# NiHAAx1to6.net
KiCad netlist of a schematic drawn in Altium Designer
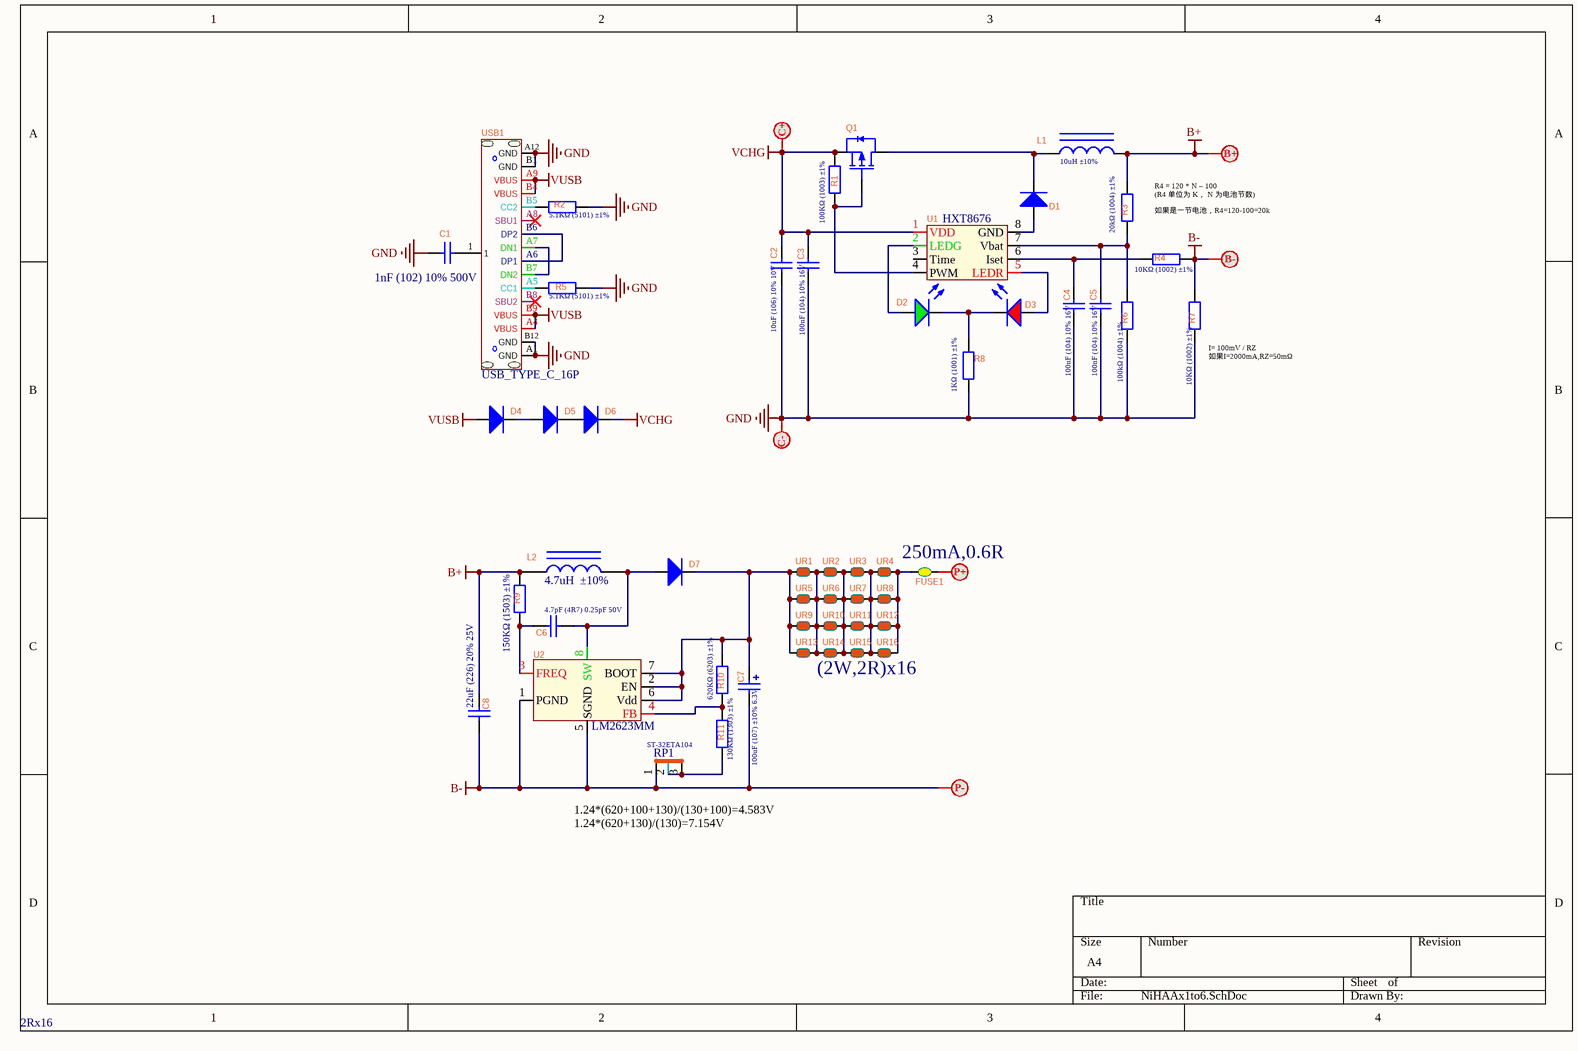
[diagram p0: NiHAAx1to6.SchDoc]

(export (version "E")
  (design (tool "Eeschema 10.0.6"))
  (components
    (comp (ref "B+1") (value "B+") (footprint "TAP") (libsource (lib "NiHAAx1to6") (part "B+")))
    (comp (ref "B-1") (value "B-") (footprint "TAP") (libsource (lib "NiHAAx1to6") (part "B-")))
    (comp (ref "C+1") (value "C+") (footprint "TAP") (libsource (lib "NiHAAx1to6") (part "C+")))
    (comp (ref "C-1") (value "C-") (footprint "TAP") (libsource (lib "NiHAAx1to6") (part "C-")))
    (comp (ref "C1")
      (value "1nF (102) 10% 500V")
      (footprint "1206_C")
      (description "贴片电容")
      (libsource (lib "Miscellaneous Devices LC") (part "1206 1nF (102) 10% 500V"))
    )
    (comp (ref "C2")
      (value "10uF (106) 10% 10V")
      (footprint "0603_C")
      (description "贴片电容")
      (libsource (lib "Miscellaneous Devices LC") (part "0603 10uF (106) 10% 10V"))
    )
    (comp (ref "C3")
      (value "100nF (104) 10% 16V")
      (footprint "0402_C")
      (description "贴片电容")
      (libsource (lib "Miscellaneous Devices LC") (part "0402 100nF (104) 10% 16V"))
    )
    (comp (ref "C4")
      (value "100nF (104) 10% 16V")
      (footprint "0402_C")
      (description "贴片电容")
      (libsource (lib "Miscellaneous Devices LC") (part "0402 100nF (104) 10% 16V"))
    )
    (comp (ref "C5")
      (value "100nF (104) 10% 16V")
      (footprint "0402_C")
      (description "贴片电容")
      (libsource (lib "Miscellaneous Devices LC") (part "0402 100nF (104) 10% 16V"))
    )
    (comp (ref "C6")
      (value "4.7pF (4R7) 0.25pF 50V")
      (footprint "0402_C")
      (description "贴片电容")
      (libsource (lib "Miscellaneous Devices LC") (part "0402 4.7pF (4R7) 0.25pF 50V"))
    )
    (comp (ref "C7")
      (value "100uF (107) ±10% 6.3V")
      (footprint "CASE-B_3528")
      (description "钽电容")
      (libsource (lib "Miscellaneous Devices LC") (part "3528 100uF (107) 10% 6.3V"))
    )
    (comp (ref "C8")
      (value "22uF (226) 20% 25V")
      (footprint "0805_C")
      (description "贴片电容")
      (libsource (lib "Miscellaneous Devices LC") (part "0805 22uF (226) 20% 25V"))
    )
    (comp (ref "D1")
      (value "M7")
      (footprint "CMS01")
      (description "二极管")
      (libsource (lib "Miscellaneous Devices LC") (part "SMA(DO-214AC) M7"))
    )
    (comp (ref "D2")
      (value "绿灯 0603")
      (footprint "0603_LED_S1")
      (description "发光二极管")
      (libsource (lib "Miscellaneous Devices LC") (part "0603 绿灯"))
    )
    (comp (ref "D3")
      (value "红灯 0603")
      (footprint "0603_LED_S1")
      (description "发光二极管")
      (libsource (lib "Miscellaneous Devices LC") (part "0603 红灯"))
    )
    (comp (ref "D4")
      (value "M7")
      (footprint "CMS01")
      (description "二极管")
      (libsource (lib "Miscellaneous Devices LC") (part "SMA(DO-214AC) M7"))
    )
    (comp (ref "D5")
      (value "M7")
      (footprint "CMS01")
      (description "二极管")
      (libsource (lib "Miscellaneous Devices LC") (part "SMA(DO-214AC) M7"))
    )
    (comp (ref "D6")
      (value "M7")
      (footprint "CMS01")
      (description "二极管")
      (libsource (lib "Miscellaneous Devices LC") (part "SMA(DO-214AC) M7"))
    )
    (comp (ref "D7")
      (value "M7")
      (footprint "CMS01")
      (description "二极管")
      (libsource (lib "Miscellaneous Devices LC") (part "SMA(DO-214AC) M7"))
    )
    (comp (ref "FUSE1")
      (value "OMF125")
      (footprint "2512")
      (description "3404.0006.22 OMF125 250mA OMF125 SCHURTER 贴装快速熔断保险丝")
      (libsource (lib "NiHAAx1to6") (part "FUSE"))
    )
    (comp (ref "L1")
      (value "10uH ±10%")
      (footprint "1206_L")
      (description "贴片电感")
      (libsource (lib "Miscellaneous Devices LC") (part "1206 10uH 10%"))
    )
    (comp (ref "L2")
      (value "4.7uH  ±10%")
      (footprint "1206_L")
      (description "贴片电感")
      (libsource (lib "Miscellaneous Devices LC") (part "1206 4.7uH  10%"))
    )
    (comp (ref "P+1") (value "P+") (footprint "TAP") (libsource (lib "NiHAAx1to6") (part "P+")))
    (comp (ref "P-1") (value "P-") (footprint "TAP") (libsource (lib "NiHAAx1to6") (part "P-")))
    (comp (ref "Q1")
      (value "AO3401A P道沟 X13A15 SOT-23")
      (footprint "SOT-23-3L")
      (description "MOS(场效应管)")
      (libsource (lib "Miscellaneous Devices LC") (part "AO3401A P道沟 X13A15 SOT-23"))
    )
    (comp (ref "R1")
      (value "100KΩ (1003) ±1%")
      (footprint "0402_R")
      (description "贴片电阻")
      (libsource (lib "Miscellaneous Devices LC") (part "0402 100KΩ (1003) 1%"))
    )
    (comp (ref "R2")
      (value "5.1KΩ (5101) ±1%")
      (footprint "0402_R")
      (description "贴片电阻")
      (libsource (lib "Miscellaneous Devices LC") (part "0402 5.1KΩ (5101) 1%"))
    )
    (comp (ref "R3")
      (value "20kΩ (1004) ±1%")
      (footprint "0402_R")
      (description "贴片电阻")
      (libsource (lib "Miscellaneous Devices LC") (part "0402 1MΩ (1004) 1%"))
    )
    (comp (ref "R4")
      (value "10KΩ (1002) ±1%")
      (footprint "0402_R")
      (description "贴片电阻")
      (libsource (lib "") (part "0402 10KΩ (1002) 1%_1"))
    )
    (comp (ref "R5")
      (value "5.1KΩ (5101) ±1%")
      (footprint "0402_R")
      (description "贴片电阻")
      (libsource (lib "Miscellaneous Devices LC") (part "0402 5.1KΩ (5101) 1%"))
    )
    (comp (ref "R6")
      (value "100kΩ (1004) ±1%")
      (footprint "0402_R")
      (description "贴片电阻")
      (libsource (lib "") (part "0402 1MΩ (1004) 1%_1"))
    )
    (comp (ref "R7")
      (value "10KΩ (1002) ±1%")
      (footprint "0805_R")
      (description "贴片电阻")
      (libsource (lib "Miscellaneous Devices LC") (part "0402 10KΩ (1002) 1%"))
    )
    (comp (ref "R8")
      (value "1KΩ (1001) ±1%")
      (footprint "0402_R")
      (description "贴片电阻")
      (libsource (lib "Miscellaneous Devices LC") (part "0402 1KΩ (1001) 1%"))
    )
    (comp (ref "R9")
      (value "150KΩ (1503) ±1%")
      (footprint "0402_R")
      (description "贴片电阻")
      (libsource (lib "Miscellaneous Devices LC") (part "0402 150KΩ (1503) 1%"))
    )
    (comp (ref "R10")
      (value "620KΩ (6203) ±1%")
      (footprint "0603_R")
      (description "贴片电阻")
      (libsource (lib "Miscellaneous Devices LC") (part "0603 620KΩ (6203) 1%"))
    )
    (comp (ref "R11")
      (value "130KΩ (1303) ±1%")
      (footprint "0603_R")
      (description "贴片电阻")
      (libsource (lib "Miscellaneous Devices LC") (part "0603 130KΩ (1303) 1%"))
    )
    (comp (ref "RP1")
      (value "ST-32ETA104")
      (footprint "ST-32ETA104")
      (description "3X3 SMD可调电阻 贴片电位器")
      (libsource (lib "NiHAAx1to6") (part "RP"))
    )
    (comp (ref "U1")
      (value "HXT8676")
      (footprint "SOP-8_150mil")
      (description "镍氢电池充电 IC")
      (libsource (lib "NiHAAx1to6") (part "HXT8676"))
    )
    (comp (ref "U2")
      (value "LM2623MM")
      (footprint "VSSOP8_3×3mm")
      (description "3 General-Purpose, Gated-Oscillator-Based DC-DC Boost Converter")
      (libsource (lib "NiHAAx1to6") (part "LM2623"))
    )
    (comp (ref "UR1") (value "R") (footprint "2512") (libsource (lib "NiHAAx1to6") (part "R")))
    (comp (ref "UR2") (value "R") (footprint "2512") (libsource (lib "NiHAAx1to6") (part "R")))
    (comp (ref "UR3") (value "R") (footprint "2512") (libsource (lib "NiHAAx1to6") (part "R")))
    (comp (ref "UR4") (value "R") (footprint "2512") (libsource (lib "NiHAAx1to6") (part "R")))
    (comp (ref "UR5") (value "R") (footprint "2512") (libsource (lib "NiHAAx1to6") (part "R")))
    (comp (ref "UR6") (value "R") (footprint "2512") (libsource (lib "NiHAAx1to6") (part "R")))
    (comp (ref "UR7") (value "R") (footprint "2512") (libsource (lib "NiHAAx1to6") (part "R")))
    (comp (ref "UR8") (value "R") (footprint "2512") (libsource (lib "NiHAAx1to6") (part "R")))
    (comp (ref "UR9") (value "R") (footprint "2512") (libsource (lib "NiHAAx1to6") (part "R")))
    (comp (ref "UR10") (value "R") (footprint "2512") (libsource (lib "NiHAAx1to6") (part "R")))
    (comp (ref "UR11") (value "R") (footprint "2512") (libsource (lib "NiHAAx1to6") (part "R")))
    (comp (ref "UR12") (value "R") (footprint "2512") (libsource (lib "NiHAAx1to6") (part "R")))
    (comp (ref "UR13") (value "R") (footprint "2512") (libsource (lib "NiHAAx1to6") (part "R")))
    (comp (ref "UR14") (value "R") (footprint "2512") (libsource (lib "NiHAAx1to6") (part "R")))
    (comp (ref "UR15") (value "R") (footprint "2512") (libsource (lib "NiHAAx1to6") (part "R")))
    (comp (ref "UR16") (value "R") (footprint "2512") (libsource (lib "NiHAAx1to6") (part "R")))
    (comp (ref "USB1")
      (value "USB_TYPE_C_16P")
      (footprint "USB Type-C-16Pin_A")
      (libsource (lib "OET") (part "USB_TYPE_C_16P"))
    )
  )
  (nets
    (net (code "1") (name "B+") (class "Default")
      (node (ref "B+1") (pin "1") (pinfunction "B+_1") (pintype "passive"))
      (node (ref "C8") (pin "2") (pinfunction "2_2") (pintype "passive"))
      (node (ref "L1") (pin "2") (pinfunction "2_2") (pintype "passive"))
      (node (ref "L2") (pin "1") (pinfunction "1_1") (pintype "passive"))
      (node (ref "R3") (pin "2") (pinfunction "2_2") (pintype "passive"))
      (node (ref "R9") (pin "2") (pinfunction "2_2") (pintype "passive"))
    )
    (net (code "2") (name "B-") (class "Default")
      (node (ref "B-1") (pin "1") (pinfunction "B-_1") (pintype "passive"))
      (node (ref "C7") (pin "2") (pinfunction "2_2") (pintype "passive"))
      (node (ref "C8") (pin "1") (pinfunction "1_1") (pintype "passive"))
      (node (ref "P-1") (pin "1") (pinfunction "P-_1") (pintype "passive"))
      (node (ref "R4") (pin "2") (pinfunction "2_2") (pintype "passive"))
      (node (ref "R7") (pin "2") (pinfunction "2_2") (pintype "passive"))
      (node (ref "RP1") (pin "1") (pintype "passive"))
      (node (ref "U2") (pin "1") (pinfunction "PGND_1") (pintype "passive"))
      (node (ref "U2") (pin "5") (pinfunction "SGND_5") (pintype "passive"))
    )
    (net (code "3") (name "GND") (class "Default")
      (node (ref "C-1") (pin "1") (pinfunction "C-_1") (pintype "passive"))
      (node (ref "C1") (pin "2") (pinfunction "2_2") (pintype "passive"))
      (node (ref "C2") (pin "1") (pinfunction "1_1") (pintype "passive"))
      (node (ref "C3") (pin "1") (pinfunction "1_1") (pintype "passive"))
      (node (ref "C4") (pin "1") (pinfunction "1_1") (pintype "passive"))
      (node (ref "C5") (pin "1") (pinfunction "1_1") (pintype "passive"))
      (node (ref "R2") (pin "1") (pinfunction "1_1") (pintype "passive"))
      (node (ref "R5") (pin "1") (pinfunction "1_1") (pintype "passive"))
      (node (ref "R6") (pin "2") (pinfunction "2_2") (pintype "passive"))
      (node (ref "R7") (pin "1") (pinfunction "1_1") (pintype "passive"))
      (node (ref "R8") (pin "1") (pinfunction "1_1") (pintype "passive"))
      (node (ref "USB1") (pin "A1") (pinfunction "GND_A1") (pintype "passive"))
      (node (ref "USB1") (pin "A12") (pinfunction "GND_A12") (pintype "passive"))
      (node (ref "USB1") (pin "B1") (pinfunction "GND_B1") (pintype "passive"))
      (node (ref "USB1") (pin "B12") (pinfunction "GND_B12") (pintype "passive"))
    )
    (net (code "4") (name "Net-(C1-Pad1)") (class "Default")
      (node (ref "C1") (pin "1") (pinfunction "1_1") (pintype "passive"))
      (node (ref "USB1") (pin "1") (pinfunction "1_1") (pintype "passive"))
    )
    (net (code "5") (name "Net-(D1-A)") (class "Default")
      (node (ref "D1") (pin "1") (pinfunction "A_1") (pintype "passive"))
      (node (ref "U1") (pin "8") (pinfunction "GND_8") (pintype "passive"))
    )
    (net (code "6") (name "Net-(D1-K)") (class "Default")
      (node (ref "D1") (pin "2") (pinfunction "K_2") (pintype "passive"))
      (node (ref "L1") (pin "1") (pinfunction "1_1") (pintype "passive"))
      (node (ref "Q1") (pin "3") (pinfunction "D_3") (pintype "passive"))
    )
    (net (code "7") (name "Net-(D2-PadK)") (class "Default")
      (node (ref "D2") (pin "K") (pinfunction "K_K") (pintype "passive"))
      (node (ref "D3") (pin "K") (pinfunction "K_K") (pintype "passive"))
      (node (ref "R8") (pin "2") (pinfunction "2_2") (pintype "passive"))
    )
    (net (code "8") (name "Net-(D4-K)") (class "Default")
      (node (ref "D4") (pin "2") (pinfunction "K_2") (pintype "passive"))
      (node (ref "D5") (pin "1") (pinfunction "A_1") (pintype "passive"))
    )
    (net (code "9") (name "Net-(D5-K)") (class "Default")
      (node (ref "D5") (pin "2") (pinfunction "K_2") (pintype "passive"))
      (node (ref "D6") (pin "1") (pinfunction "A_1") (pintype "passive"))
    )
    (net (code "10") (name "Net-(D7-A)") (class "Default")
      (node (ref "C6") (pin "2") (pinfunction "2_2") (pintype "passive"))
      (node (ref "D7") (pin "1") (pinfunction "A_1") (pintype "passive"))
      (node (ref "L2") (pin "2") (pinfunction "2_2") (pintype "passive"))
      (node (ref "U2") (pin "8") (pinfunction "SW_8") (pintype "passive"))
    )
    (net (code "11") (name "Net-(D7-K)") (class "Default")
      (node (ref "C7") (pin "1") (pinfunction "1_1") (pintype "passive"))
      (node (ref "D7") (pin "2") (pinfunction "K_2") (pintype "passive"))
      (node (ref "R10") (pin "2") (pinfunction "2_2") (pintype "passive"))
      (node (ref "U2") (pin "2") (pinfunction "EN_2") (pintype "passive"))
      (node (ref "U2") (pin "6") (pinfunction "Vdd_6") (pintype "passive"))
      (node (ref "U2") (pin "7") (pinfunction "BOOT_7") (pintype "passive"))
      (node (ref "UR1") (pin "1") (pintype "passive"))
      (node (ref "UR13") (pin "1") (pintype "passive"))
      (node (ref "UR5") (pin "1") (pintype "passive"))
      (node (ref "UR9") (pin "1") (pintype "passive"))
    )
    (net (code "12") (name "Net-(FUSE1-Pad2)") (class "Default")
      (node (ref "FUSE1") (pin "2") (pintype "passive"))
      (node (ref "UR12") (pin "2") (pintype "passive"))
      (node (ref "UR16") (pin "2") (pintype "passive"))
      (node (ref "UR4") (pin "2") (pintype "passive"))
      (node (ref "UR8") (pin "2") (pintype "passive"))
    )
    (net (code "13") (name "Net-(P+1-P+)") (class "Default")
      (node (ref "FUSE1") (pin "1") (pintype "passive"))
      (node (ref "P+1") (pin "1") (pinfunction "P+_1") (pintype "passive"))
    )
    (net (code "14") (name "Net-(Q1-G)") (class "Default")
      (node (ref "Q1") (pin "1") (pinfunction "G_1") (pintype "passive"))
      (node (ref "R1") (pin "1") (pinfunction "1_1") (pintype "passive"))
      (node (ref "U1") (pin "4") (pinfunction "PWM_4") (pintype "passive"))
    )
    (net (code "15") (name "Net-(R11-Pad1)") (class "Default")
      (node (ref "R11") (pin "1") (pinfunction "1_1") (pintype "passive"))
      (node (ref "RP1") (pin "2") (pintype "passive"))
      (node (ref "RP1") (pin "3") (pintype "passive"))
    )
    (net (code "16") (name "Net-(U1-Iset)") (class "Default")
      (node (ref "C4") (pin "2") (pinfunction "2_2") (pintype "passive"))
      (node (ref "R4") (pin "1") (pinfunction "1_1") (pintype "passive"))
      (node (ref "U1") (pin "6") (pinfunction "Iset_6") (pintype "passive"))
    )
    (net (code "17") (name "Net-(U1-LEDG)") (class "Default")
      (node (ref "D2") (pin "A") (pinfunction "A_A") (pintype "passive"))
      (node (ref "U1") (pin "2") (pinfunction "LEDG_2") (pintype "passive"))
    )
    (net (code "18") (name "Net-(U1-LEDR)") (class "Default")
      (node (ref "D3") (pin "A") (pinfunction "A_A") (pintype "passive"))
      (node (ref "U1") (pin "5") (pinfunction "LEDR_5") (pintype "passive"))
    )
    (net (code "19") (name "Net-(U1-Vbat)") (class "Default")
      (node (ref "C5") (pin "2") (pinfunction "2_2") (pintype "passive"))
      (node (ref "R3") (pin "1") (pinfunction "1_1") (pintype "passive"))
      (node (ref "R6") (pin "1") (pinfunction "1_1") (pintype "passive"))
      (node (ref "U1") (pin "7") (pinfunction "Vbat_7") (pintype "passive"))
    )
    (net (code "20") (name "Net-(U2-FB)") (class "Default")
      (node (ref "R10") (pin "1") (pinfunction "1_1") (pintype "passive"))
      (node (ref "R11") (pin "2") (pinfunction "2_2") (pintype "passive"))
      (node (ref "U2") (pin "4") (pinfunction "FB_4") (pintype "passive"))
    )
    (net (code "21") (name "Net-(U2-FREQ)") (class "Default")
      (node (ref "C6") (pin "1") (pinfunction "1_1") (pintype "passive"))
      (node (ref "R9") (pin "1") (pinfunction "1_1") (pintype "passive"))
      (node (ref "U2") (pin "3") (pinfunction "FREQ_3") (pintype "passive"))
    )
    (net (code "22") (name "Net-(UR1-Pad2)") (class "Default")
      (node (ref "UR1") (pin "2") (pintype "passive"))
      (node (ref "UR10") (pin "1") (pintype "passive"))
      (node (ref "UR13") (pin "2") (pintype "passive"))
      (node (ref "UR14") (pin "1") (pintype "passive"))
      (node (ref "UR2") (pin "1") (pintype "passive"))
      (node (ref "UR5") (pin "2") (pintype "passive"))
      (node (ref "UR6") (pin "1") (pintype "passive"))
      (node (ref "UR9") (pin "2") (pintype "passive"))
    )
    (net (code "23") (name "Net-(UR10-Pad2)") (class "Default")
      (node (ref "UR10") (pin "2") (pintype "passive"))
      (node (ref "UR11") (pin "1") (pintype "passive"))
      (node (ref "UR14") (pin "2") (pintype "passive"))
      (node (ref "UR15") (pin "1") (pintype "passive"))
      (node (ref "UR2") (pin "2") (pintype "passive"))
      (node (ref "UR3") (pin "1") (pintype "passive"))
      (node (ref "UR6") (pin "2") (pintype "passive"))
      (node (ref "UR7") (pin "1") (pintype "passive"))
    )
    (net (code "24") (name "Net-(UR11-Pad2)") (class "Default")
      (node (ref "UR11") (pin "2") (pintype "passive"))
      (node (ref "UR12") (pin "1") (pintype "passive"))
      (node (ref "UR15") (pin "2") (pintype "passive"))
      (node (ref "UR16") (pin "1") (pintype "passive"))
      (node (ref "UR3") (pin "2") (pintype "passive"))
      (node (ref "UR4") (pin "1") (pintype "passive"))
      (node (ref "UR7") (pin "2") (pintype "passive"))
      (node (ref "UR8") (pin "1") (pintype "passive"))
    )
    (net (code "25") (name "Net-(USB1-CC1)") (class "Default")
      (node (ref "R5") (pin "2") (pinfunction "2_2") (pintype "passive"))
      (node (ref "USB1") (pin "A5") (pinfunction "CC1_A5") (pintype "passive"))
    )
    (net (code "26") (name "Net-(USB1-CC2)") (class "Default")
      (node (ref "R2") (pin "2") (pinfunction "2_2") (pintype "passive"))
      (node (ref "USB1") (pin "B5") (pinfunction "CC2_B5") (pintype "passive"))
    )
    (net (code "27") (name "Net-(USB1-DN1)") (class "Default")
      (node (ref "USB1") (pin "A7") (pinfunction "DN1_A7") (pintype "passive"))
      (node (ref "USB1") (pin "B7") (pinfunction "DN2_B7") (pintype "passive"))
    )
    (net (code "28") (name "Net-(USB1-DP1)") (class "Default")
      (node (ref "USB1") (pin "A6") (pinfunction "DP1_A6") (pintype "passive"))
      (node (ref "USB1") (pin "B6") (pinfunction "DP2_B6") (pintype "passive"))
    )
    (net (code "29") (name "VCHG") (class "Default")
      (node (ref "C+1") (pin "1") (pinfunction "C+_1") (pintype "passive"))
      (node (ref "C2") (pin "2") (pinfunction "2_2") (pintype "passive"))
      (node (ref "C3") (pin "2") (pinfunction "2_2") (pintype "passive"))
      (node (ref "D6") (pin "2") (pinfunction "K_2") (pintype "passive"))
      (node (ref "Q1") (pin "2") (pinfunction "S_2") (pintype "passive"))
      (node (ref "R1") (pin "2") (pinfunction "2_2") (pintype "passive"))
      (node (ref "U1") (pin "1") (pinfunction "VDD_1") (pintype "passive"))
    )
    (net (code "30") (name "VUSB") (class "Default")
      (node (ref "D4") (pin "1") (pinfunction "A_1") (pintype "passive"))
      (node (ref "USB1") (pin "A4") (pinfunction "VBUS_A4") (pintype "passive"))
      (node (ref "USB1") (pin "A9") (pinfunction "VBUS_A9") (pintype "passive"))
      (node (ref "USB1") (pin "B4") (pinfunction "VBUS_B4") (pintype "passive"))
      (node (ref "USB1") (pin "B9") (pinfunction "VBUS_B9") (pintype "passive"))
    )
    (net (code "31") (name "unconnected-(U1-Time-Pad3)") (class "Default")
      (node (ref "U1") (pin "3") (pinfunction "Time_3") (pintype "passive"))
    )
    (net (code "32") (name "unconnected-(USB1-SBU1-PadA8)") (class "Default")
      (node (ref "USB1") (pin "A8") (pinfunction "SBU1_A8") (pintype "passive+no_connect"))
    )
    (net (code "33") (name "unconnected-(USB1-SBU2-PadB8)") (class "Default")
      (node (ref "USB1") (pin "B8") (pinfunction "SBU2_B8") (pintype "passive+no_connect"))
    )
  )
)
